# DSO_Control.net
KiCad netlist of a schematic drawn in Altium Designer
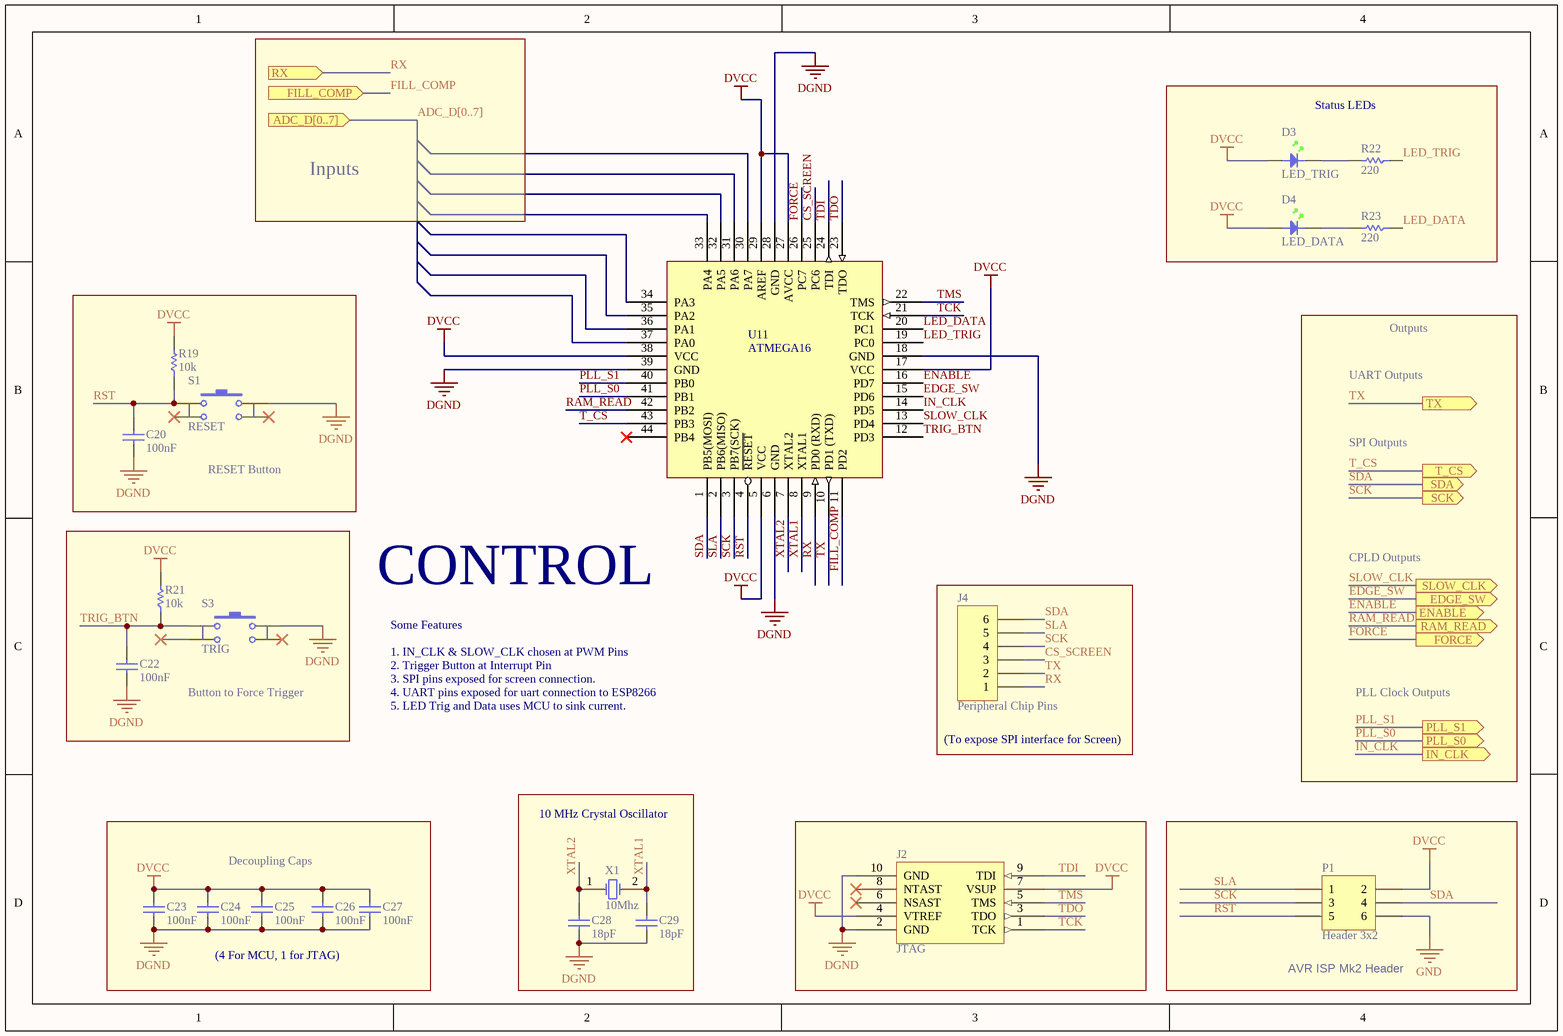
[diagram p0: DSO_Control.SchDoc]

(export (version "E")
  (design (tool "Eeschema 10.0.6"))
  (components
    (comp (ref "C20")
      (value "100nF")
      (footprint "0805C")
      (description "Capacitor")
      (fields (field (name "REVIEWED BY") "RM - 2018/08/05"))
      (libsource (lib "DSO") (part "C"))
    )
    (comp (ref "C22")
      (value "100nF")
      (footprint "0805C")
      (description "Capacitor")
      (fields (field (name "REVIEWED BY") "RM - 2018/08/05"))
      (libsource (lib "DSO") (part "C"))
    )
    (comp (ref "C23")
      (value "100nF")
      (footprint "0805C")
      (description "Capacitor")
      (fields (field (name "REVIEWED BY") "RM - 2018/08/05"))
      (libsource (lib "DSO") (part "C"))
    )
    (comp (ref "C24")
      (value "100nF")
      (footprint "0805C")
      (description "Capacitor")
      (fields (field (name "REVIEWED BY") "RM - 2018/08/05"))
      (libsource (lib "DSO") (part "C"))
    )
    (comp (ref "C25")
      (value "100nF")
      (footprint "0805C")
      (description "Capacitor")
      (fields (field (name "REVIEWED BY") "RM - 2018/08/05"))
      (libsource (lib "DSO") (part "C"))
    )
    (comp (ref "C26")
      (value "100nF")
      (footprint "0805C")
      (description "Capacitor")
      (fields (field (name "REVIEWED BY") "RM - 2018/08/05"))
      (libsource (lib "DSO") (part "C"))
    )
    (comp (ref "C27")
      (value "100nF")
      (footprint "0805C")
      (description "Capacitor")
      (fields (field (name "REVIEWED BY") "RM - 2018/08/05"))
      (libsource (lib "DSO") (part "C"))
    )
    (comp (ref "C28")
      (value "18pF")
      (footprint "0805C")
      (description "Capacitor")
      (fields (field (name "REVIEWED BY") "RM - 2018/08/05"))
      (libsource (lib "DSO") (part "C"))
    )
    (comp (ref "C29")
      (value "18pF")
      (footprint "0805C")
      (description "Capacitor")
      (fields (field (name "REVIEWED BY") "RM - 2018/08/05"))
      (libsource (lib "DSO") (part "C"))
    )
    (comp (ref "D3")
      (value "LED_TRIG")
      (footprint "0805D-GREEN")
      (description "Light Emitting Diode")
      (fields (field (name "REVIEWED BY") "RM - 2018/08/05"))
      (libsource (lib "DSO") (part "LED GREEN"))
    )
    (comp (ref "D4")
      (value "LED_DATA")
      (footprint "0805D-GREEN")
      (description "Light Emitting Diode")
      (fields (field (name "REVIEWED BY") "RM - 2018/08/05"))
      (libsource (lib "DSO") (part "LED GREEN"))
    )
    (comp (ref "J2")
      (value "JTAG")
      (footprint "BOXEDVERT10")
      (description "JTAG_CON")
      (fields (field (name "REVIEWED BY") "RM - 2018/08/05"))
      (libsource (lib "DSO") (part "JTAG_CON"))
    )
    (comp (ref "J4")
      (value "Peripheral Chip Pins")
      (footprint "HDR1X6")
      (description "Header, 6-Pin")
      (libsource (lib "DSO") (part "Header 6"))
    )
    (comp (ref "P1")
      (value "Header 3x2")
      (footprint "HDR3x2")
      (description "Header, 5-Pin")
      (fields (field (name "REVIEWED BY") "RM - 2018/08/05"))
      (libsource (lib "DSO") (part "Header 3x2"))
    )
    (comp (ref "R19")
      (value "10k")
      (footprint "0805")
      (description "Resistor")
      (fields (field (name "REVIEWED BY") "RM - 2018/08/05"))
      (libsource (lib "DSO") (part "R"))
    )
    (comp (ref "R21")
      (value "10k")
      (footprint "0805")
      (description "Resistor")
      (fields (field (name "REVIEWED BY") "RM - 2018/08/05"))
      (libsource (lib "DSO") (part "R"))
    )
    (comp (ref "R22")
      (value "220")
      (footprint "0805")
      (description "Resistor")
      (fields (field (name "REVIEWED BY") "RM - 2018/08/05"))
      (libsource (lib "DSO") (part "R"))
    )
    (comp (ref "R23")
      (value "220")
      (footprint "0805")
      (description "Resistor")
      (fields (field (name "REVIEWED BY") "RM - 2018/08/05"))
      (libsource (lib "DSO") (part "R"))
    )
    (comp (ref "S1")
      (value "RESET")
      (footprint "SPST PB SWITCH SMD")
      (description "Momentary Push Button Switch 1P 1T 2pins")
      (fields (field (name "REVIEWED BY") "RM - 2018/08/05"))
      (libsource (lib "DSO") (part "SW_PB_1P1T4"))
    )
    (comp (ref "S3")
      (value "TRIG")
      (footprint "SPST PB SWITCH SMD")
      (description "Momentary Push Button Switch 1P 1T 2pins")
      (fields (field (name "REVIEWED BY") "RM - 2018/08/05"))
      (libsource (lib "DSO") (part "SW_PB_1P1T4"))
    )
    (comp (ref "U11")
      (value "ATMEGA16")
      (footprint "QFP-48")
      (description "ATMEGA16 Microcontroller")
      (fields (field (name "REVIEWED BY") "RM - 2018/08/05"))
      (libsource (lib "DSO") (part "ATMEGA16"))
    )
    (comp (ref "X1")
      (value "10Mhz")
      (footprint "XTAL_FLAT_SMD")
      (description "Crystal Oscillator")
      (fields (field (name "REVIEWED BY") "RM - 2018/08/05"))
      (libsource (lib "DSO") (part "XTAL"))
    )
  )
  (nets
    (net (code "10") (name "/CS_SCREEN") (class "Default")
      (node (ref "J4") (pin "3") (pinfunction "3_3") (pintype "passive"))
      (node (ref "U11") (pin "25") (pinfunction "PC6_25") (pintype "passive"))
    )
    (net (code "11") (name "/EDGE_SW") (class "Default")
      (node (ref "U11") (pin "15") (pinfunction "PD6_15") (pintype "passive"))
    )
    (net (code "12") (name "/ENABLE") (class "Default")
      (node (ref "U11") (pin "16") (pinfunction "PD7_16") (pintype "passive"))
    )
    (net (code "13") (name "/FILL_COMP") (class "Default")
      (node (ref "U11") (pin "11") (pinfunction "PD2_11") (pintype "passive"))
    )
    (net (code "14") (name "/FORCE") (class "Default")
      (node (ref "U11") (pin "26") (pinfunction "PC7_26") (pintype "passive"))
    )
    (net (code "15") (name "/IN_CLK") (class "Default")
      (node (ref "U11") (pin "14") (pinfunction "PD5_14") (pintype "passive"))
    )
    (net (code "16") (name "/LED_DATA") (class "Default")
      (node (ref "R23") (pin "1") (pintype "passive"))
      (node (ref "U11") (pin "20") (pinfunction "PC1_20") (pintype "passive"))
    )
    (net (code "17") (name "/LED_TRIG") (class "Default")
      (node (ref "R22") (pin "1") (pintype "passive"))
      (node (ref "U11") (pin "19") (pinfunction "PC0_19") (pintype "passive"))
    )
    (net (code "18") (name "/PLL_S0") (class "Default")
      (node (ref "U11") (pin "41") (pinfunction "PB1_41") (pintype "passive"))
    )
    (net (code "19") (name "/PLL_S1") (class "Default")
      (node (ref "U11") (pin "40") (pinfunction "PB0_40") (pintype "passive"))
    )
    (net (code "20") (name "/RAM_READ") (class "Default")
      (node (ref "U11") (pin "42") (pinfunction "PB2_42") (pintype "passive"))
    )
    (net (code "21") (name "/RST") (class "Default")
      (node (ref "C20") (pin "1") (pinfunction "1_1") (pintype "passive"))
      (node (ref "P1") (pin "5") (pinfunction "5_5") (pintype "passive"))
      (node (ref "R19") (pin "1") (pintype "passive"))
      (node (ref "S1") (pin "1") (pinfunction "1_1") (pintype "passive"))
      (node (ref "U11") (pin "4") (pinfunction "~{RESET}_4") (pintype "passive"))
    )
    (net (code "22") (name "/RX") (class "Default")
      (node (ref "J4") (pin "1") (pinfunction "1_1") (pintype "passive"))
      (node (ref "U11") (pin "9") (pinfunction "PD0_(RXD)_9") (pintype "input"))
    )
    (net (code "23") (name "/SCK") (class "Default")
      (node (ref "J4") (pin "4") (pinfunction "4_4") (pintype "passive"))
      (node (ref "P1") (pin "3") (pinfunction "3_3") (pintype "passive"))
      (node (ref "U11") (pin "3") (pinfunction "PB7(SCK)_3") (pintype "passive"))
    )
    (net (code "24") (name "/SDA") (class "Default")
      (node (ref "J4") (pin "6") (pinfunction "6_6") (pintype "passive"))
      (node (ref "P1") (pin "4") (pinfunction "4_4") (pintype "passive"))
      (node (ref "U11") (pin "1") (pinfunction "PB5(MOSI)_1") (pintype "passive"))
    )
    (net (code "25") (name "/SLA") (class "Default")
      (node (ref "J4") (pin "5") (pinfunction "5_5") (pintype "passive"))
      (node (ref "P1") (pin "1") (pinfunction "1_1") (pintype "passive"))
      (node (ref "U11") (pin "2") (pinfunction "PB6(MISO)_2") (pintype "passive"))
    )
    (net (code "26") (name "/SLOW_CLK") (class "Default")
      (node (ref "U11") (pin "13") (pinfunction "PD4_13") (pintype "passive"))
    )
    (net (code "27") (name "/TCK") (class "Default")
      (node (ref "J2") (pin "1") (pinfunction "TCK_1") (pintype "output"))
      (node (ref "U11") (pin "21") (pinfunction "TCK_21") (pintype "input"))
    )
    (net (code "28") (name "/TDI") (class "Default")
      (node (ref "J2") (pin "9") (pinfunction "TDI_9") (pintype "input"))
      (node (ref "U11") (pin "24") (pinfunction "TDI_24") (pintype "output"))
    )
    (net (code "29") (name "/TDO") (class "Default")
      (node (ref "J2") (pin "3") (pinfunction "TDO_3") (pintype "output"))
      (node (ref "U11") (pin "23") (pinfunction "TDO_23") (pintype "input"))
    )
    (net (code "30") (name "/TMS") (class "Default")
      (node (ref "J2") (pin "5") (pinfunction "TMS_5") (pintype "input"))
      (node (ref "U11") (pin "22") (pinfunction "TMS_22") (pintype "output"))
    )
    (net (code "31") (name "/TRIG_BTN") (class "Default")
      (node (ref "C22") (pin "1") (pinfunction "1_1") (pintype "passive"))
      (node (ref "R21") (pin "1") (pintype "passive"))
      (node (ref "S3") (pin "1") (pinfunction "1_1") (pintype "passive"))
      (node (ref "U11") (pin "12") (pinfunction "PD3_12") (pintype "passive"))
    )
    (net (code "32") (name "/TX") (class "Default")
      (node (ref "J4") (pin "2") (pinfunction "2_2") (pintype "passive"))
      (node (ref "U11") (pin "10") (pinfunction "PD1_(TXD)_10") (pintype "output"))
    )
    (net (code "33") (name "/T_CS") (class "Default")
      (node (ref "U11") (pin "43") (pinfunction "PB3_43") (pintype "passive"))
    )
    (net (code "34") (name "/XTAL1") (class "Default")
      (node (ref "C29") (pin "1") (pinfunction "1_1") (pintype "passive"))
      (node (ref "U11") (pin "8") (pinfunction "XTAL1_8") (pintype "passive"))
      (node (ref "X1") (pin "2") (pinfunction "OSC2_2") (pintype "passive"))
    )
    (net (code "35") (name "/XTAL2") (class "Default")
      (node (ref "C28") (pin "1") (pinfunction "1_1") (pintype "passive"))
      (node (ref "U11") (pin "7") (pinfunction "XTAL2_7") (pintype "passive"))
      (node (ref "X1") (pin "1") (pinfunction "OSC1_1") (pintype "passive"))
    )
    (net (code "36") (name "DGND") (class "Default")
      (node (ref "C20") (pin "2") (pinfunction "2_2") (pintype "passive"))
      (node (ref "C22") (pin "2") (pinfunction "2_2") (pintype "passive"))
      (node (ref "C23") (pin "2") (pinfunction "2_2") (pintype "passive"))
      (node (ref "C24") (pin "2") (pinfunction "2_2") (pintype "passive"))
      (node (ref "C25") (pin "2") (pinfunction "2_2") (pintype "passive"))
      (node (ref "C26") (pin "2") (pinfunction "2_2") (pintype "passive"))
      (node (ref "C27") (pin "2") (pinfunction "2_2") (pintype "passive"))
      (node (ref "C28") (pin "2") (pinfunction "2_2") (pintype "passive"))
      (node (ref "C29") (pin "2") (pinfunction "2_2") (pintype "passive"))
      (node (ref "J2") (pin "10") (pinfunction "GND_10") (pintype "passive"))
      (node (ref "J2") (pin "2") (pinfunction "GND_2") (pintype "passive"))
      (node (ref "S1") (pin "2") (pinfunction "2_2") (pintype "passive"))
      (node (ref "S3") (pin "2") (pinfunction "2_2") (pintype "passive"))
      (node (ref "U11") (pin "18") (pinfunction "GND_18") (pintype "passive"))
      (node (ref "U11") (pin "28") (pinfunction "GND_28") (pintype "passive"))
      (node (ref "U11") (pin "39") (pinfunction "GND_39") (pintype "passive"))
      (node (ref "U11") (pin "6") (pinfunction "GND_6") (pintype "passive"))
    )
    (net (code "37") (name "DVCC") (class "Default")
      (node (ref "C23") (pin "1") (pinfunction "1_1") (pintype "passive"))
      (node (ref "C24") (pin "1") (pinfunction "1_1") (pintype "passive"))
      (node (ref "C25") (pin "1") (pinfunction "1_1") (pintype "passive"))
      (node (ref "C26") (pin "1") (pinfunction "1_1") (pintype "passive"))
      (node (ref "C27") (pin "1") (pinfunction "1_1") (pintype "passive"))
      (node (ref "D3") (pin "A") (pinfunction "A_A") (pintype "passive"))
      (node (ref "D4") (pin "A") (pinfunction "A_A") (pintype "passive"))
      (node (ref "J2") (pin "4") (pinfunction "VTREF_4") (pintype "power_in"))
      (node (ref "J2") (pin "7") (pinfunction "VSUP_7") (pintype "passive"))
      (node (ref "P1") (pin "2") (pinfunction "2_2") (pintype "passive"))
      (node (ref "R19") (pin "2") (pintype "passive"))
      (node (ref "R21") (pin "2") (pintype "passive"))
      (node (ref "U11") (pin "17") (pinfunction "VCC_17") (pintype "passive"))
      (node (ref "U11") (pin "27") (pinfunction "AVCC_27") (pintype "passive"))
      (node (ref "U11") (pin "29") (pinfunction "AREF_29") (pintype "passive"))
      (node (ref "U11") (pin "38") (pinfunction "VCC_38") (pintype "passive"))
      (node (ref "U11") (pin "5") (pinfunction "VCC_5") (pintype "passive"))
    )
    (net (code "38") (name "GND") (class "Default")
      (node (ref "P1") (pin "6") (pinfunction "6_6") (pintype "passive"))
    )
    (net (code "39") (name "Net-(D3-PadK)") (class "Default")
      (node (ref "D3") (pin "K") (pinfunction "K_K") (pintype "passive"))
      (node (ref "R22") (pin "2") (pintype "passive"))
    )
    (net (code "40") (name "Net-(D4-PadK)") (class "Default")
      (node (ref "D4") (pin "K") (pinfunction "K_K") (pintype "passive"))
      (node (ref "R23") (pin "2") (pintype "passive"))
    )
    (net (code "41") (name "unconnected-(J2-NSAST-Pad6)") (class "Default")
      (node (ref "J2") (pin "6") (pinfunction "NSAST_6") (pintype "passive+no_connect"))
    )
    (net (code "42") (name "unconnected-(J2-NTAST-Pad8)") (class "Default")
      (node (ref "J2") (pin "8") (pinfunction "NTAST_8") (pintype "passive+no_connect"))
    )
    (net (code "43") (name "unconnected-(S1-Pad3)") (class "Default")
      (node (ref "S1") (pin "3") (pinfunction "3_3") (pintype "passive+no_connect"))
    )
    (net (code "44") (name "unconnected-(S1-Pad4)") (class "Default")
      (node (ref "S1") (pin "4") (pinfunction "4_4") (pintype "passive+no_connect"))
    )
    (net (code "45") (name "unconnected-(S3-Pad3)") (class "Default")
      (node (ref "S3") (pin "3") (pinfunction "3_3") (pintype "passive+no_connect"))
    )
    (net (code "46") (name "unconnected-(S3-Pad4)") (class "Default")
      (node (ref "S3") (pin "4") (pinfunction "4_4") (pintype "passive+no_connect"))
    )
    (net (code "47") (name "unconnected-(U11-PA0-Pad37)") (class "Default")
      (node (ref "U11") (pin "37") (pinfunction "PA0_37") (pintype "passive"))
    )
    (net (code "48") (name "unconnected-(U11-PA1-Pad36)") (class "Default")
      (node (ref "U11") (pin "36") (pinfunction "PA1_36") (pintype "passive"))
    )
    (net (code "49") (name "unconnected-(U11-PA2-Pad35)") (class "Default")
      (node (ref "U11") (pin "35") (pinfunction "PA2_35") (pintype "passive"))
    )
    (net (code "50") (name "unconnected-(U11-PA3-Pad34)") (class "Default")
      (node (ref "U11") (pin "34") (pinfunction "PA3_34") (pintype "passive"))
    )
    (net (code "51") (name "unconnected-(U11-PA4-Pad33)") (class "Default")
      (node (ref "U11") (pin "33") (pinfunction "PA4_33") (pintype "passive"))
    )
    (net (code "52") (name "unconnected-(U11-PA5-Pad32)") (class "Default")
      (node (ref "U11") (pin "32") (pinfunction "PA5_32") (pintype "passive"))
    )
    (net (code "53") (name "unconnected-(U11-PA6-Pad31)") (class "Default")
      (node (ref "U11") (pin "31") (pinfunction "PA6_31") (pintype "passive"))
    )
    (net (code "54") (name "unconnected-(U11-PA7-Pad30)") (class "Default")
      (node (ref "U11") (pin "30") (pinfunction "PA7_30") (pintype "passive"))
    )
    (net (code "55") (name "unconnected-(U11-PB4-Pad44)") (class "Default")
      (node (ref "U11") (pin "44") (pinfunction "PB4_44") (pintype "passive+no_connect"))
    )
  )
)
